# keypad.net
KiCad netlist of a schematic drawn in EAGLE
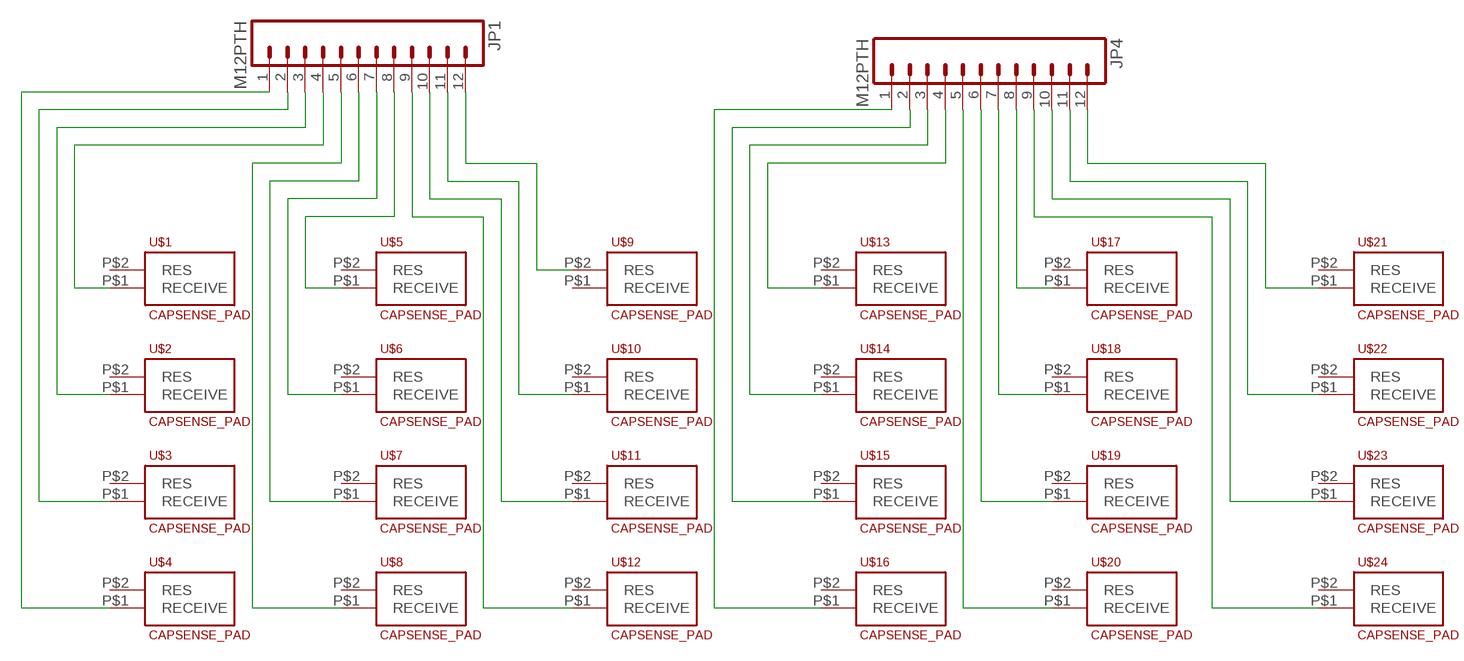
[diagram p0: schematic, sheet 1]

(export (version "E")
  (design (tool "Eeschema 10.0.6"))
  (components
    (comp (ref "JP1")
      (value "M12PTH")
      (footprint "eagle-import:1X12")
      (libsource (lib "eagle-import") (part "M12PTH"))
    )
    (comp (ref "JP4")
      (value "M12PTH")
      (footprint "eagle-import:1X12")
      (libsource (lib "eagle-import") (part "M12PTH"))
    )
    (comp (ref "U$1")
      (value "CAPSENSE_PAD")
      (footprint "eagle-import:CAPSENSE_PAD")
      (libsource (lib "eagle-import") (part "CAPSENSE_PAD"))
    )
    (comp (ref "U$2")
      (value "CAPSENSE_PAD")
      (footprint "eagle-import:CAPSENSE_PAD")
      (libsource (lib "eagle-import") (part "CAPSENSE_PAD"))
    )
    (comp (ref "U$3")
      (value "CAPSENSE_PAD")
      (footprint "eagle-import:CAPSENSE_PAD")
      (libsource (lib "eagle-import") (part "CAPSENSE_PAD"))
    )
    (comp (ref "U$4")
      (value "CAPSENSE_PAD")
      (footprint "eagle-import:CAPSENSE_PAD")
      (libsource (lib "eagle-import") (part "CAPSENSE_PAD"))
    )
    (comp (ref "U$5")
      (value "CAPSENSE_PAD")
      (footprint "eagle-import:CAPSENSE_PAD")
      (libsource (lib "eagle-import") (part "CAPSENSE_PAD"))
    )
    (comp (ref "U$6")
      (value "CAPSENSE_PAD")
      (footprint "eagle-import:CAPSENSE_PAD")
      (libsource (lib "eagle-import") (part "CAPSENSE_PAD"))
    )
    (comp (ref "U$7")
      (value "CAPSENSE_PAD")
      (footprint "eagle-import:CAPSENSE_PAD")
      (libsource (lib "eagle-import") (part "CAPSENSE_PAD"))
    )
    (comp (ref "U$8")
      (value "CAPSENSE_PAD")
      (footprint "eagle-import:CAPSENSE_PAD")
      (libsource (lib "eagle-import") (part "CAPSENSE_PAD"))
    )
    (comp (ref "U$9")
      (value "CAPSENSE_PAD")
      (footprint "eagle-import:CAPSENSE_PAD")
      (libsource (lib "eagle-import") (part "CAPSENSE_PAD"))
    )
    (comp (ref "U$10")
      (value "CAPSENSE_PAD")
      (footprint "eagle-import:CAPSENSE_PAD")
      (libsource (lib "eagle-import") (part "CAPSENSE_PAD"))
    )
    (comp (ref "U$11")
      (value "CAPSENSE_PAD")
      (footprint "eagle-import:CAPSENSE_PAD")
      (libsource (lib "eagle-import") (part "CAPSENSE_PAD"))
    )
    (comp (ref "U$12")
      (value "CAPSENSE_PAD")
      (footprint "eagle-import:CAPSENSE_PAD")
      (libsource (lib "eagle-import") (part "CAPSENSE_PAD"))
    )
    (comp (ref "U$13")
      (value "CAPSENSE_PAD")
      (footprint "eagle-import:CAPSENSE_PAD")
      (libsource (lib "eagle-import") (part "CAPSENSE_PAD"))
    )
    (comp (ref "U$14")
      (value "CAPSENSE_PAD")
      (footprint "eagle-import:CAPSENSE_PAD")
      (libsource (lib "eagle-import") (part "CAPSENSE_PAD"))
    )
    (comp (ref "U$15")
      (value "CAPSENSE_PAD")
      (footprint "eagle-import:CAPSENSE_PAD")
      (libsource (lib "eagle-import") (part "CAPSENSE_PAD"))
    )
    (comp (ref "U$16")
      (value "CAPSENSE_PAD")
      (footprint "eagle-import:CAPSENSE_PAD")
      (libsource (lib "eagle-import") (part "CAPSENSE_PAD"))
    )
    (comp (ref "U$17")
      (value "CAPSENSE_PAD")
      (footprint "eagle-import:CAPSENSE_PAD")
      (libsource (lib "eagle-import") (part "CAPSENSE_PAD"))
    )
    (comp (ref "U$18")
      (value "CAPSENSE_PAD")
      (footprint "eagle-import:CAPSENSE_PAD")
      (libsource (lib "eagle-import") (part "CAPSENSE_PAD"))
    )
    (comp (ref "U$19")
      (value "CAPSENSE_PAD")
      (footprint "eagle-import:CAPSENSE_PAD")
      (libsource (lib "eagle-import") (part "CAPSENSE_PAD"))
    )
    (comp (ref "U$20")
      (value "CAPSENSE_PAD")
      (footprint "eagle-import:CAPSENSE_PAD")
      (libsource (lib "eagle-import") (part "CAPSENSE_PAD"))
    )
    (comp (ref "U$21")
      (value "CAPSENSE_PAD")
      (footprint "eagle-import:CAPSENSE_PAD")
      (libsource (lib "eagle-import") (part "CAPSENSE_PAD"))
    )
    (comp (ref "U$22")
      (value "CAPSENSE_PAD")
      (footprint "eagle-import:CAPSENSE_PAD")
      (libsource (lib "eagle-import") (part "CAPSENSE_PAD"))
    )
    (comp (ref "U$23")
      (value "CAPSENSE_PAD")
      (footprint "eagle-import:CAPSENSE_PAD")
      (libsource (lib "eagle-import") (part "CAPSENSE_PAD"))
    )
    (comp (ref "U$24")
      (value "CAPSENSE_PAD")
      (footprint "eagle-import:CAPSENSE_PAD")
      (libsource (lib "eagle-import") (part "CAPSENSE_PAD"))
    )
  )
  (nets
    (net (code "1") (name "Net-(U$1-RECEIVE)") (class "Default")
      (node (ref "JP1") (pin "4") (pinfunction "4_4") (pintype "passive"))
      (node (ref "U$1") (pin "P$1") (pinfunction "RECEIVE_P$1") (pintype "bidirectional"))
    )
    (net (code "2") (name "Net-(U$2-RECEIVE)") (class "Default")
      (node (ref "JP1") (pin "3") (pinfunction "3_3") (pintype "passive"))
      (node (ref "U$2") (pin "P$1") (pinfunction "RECEIVE_P$1") (pintype "bidirectional"))
    )
    (net (code "3") (name "Net-(U$3-RECEIVE)") (class "Default")
      (node (ref "JP1") (pin "2") (pinfunction "2_2") (pintype "passive"))
      (node (ref "U$3") (pin "P$1") (pinfunction "RECEIVE_P$1") (pintype "bidirectional"))
    )
    (net (code "4") (name "Net-(U$4-RECEIVE)") (class "Default")
      (node (ref "JP1") (pin "1") (pinfunction "1_1") (pintype "passive"))
      (node (ref "U$4") (pin "P$1") (pinfunction "RECEIVE_P$1") (pintype "bidirectional"))
    )
    (net (code "5") (name "Net-(U$5-RECEIVE)") (class "Default")
      (node (ref "JP1") (pin "8") (pinfunction "8_8") (pintype "passive"))
      (node (ref "U$5") (pin "P$1") (pinfunction "RECEIVE_P$1") (pintype "bidirectional"))
    )
    (net (code "6") (name "Net-(U$6-RECEIVE)") (class "Default")
      (node (ref "JP1") (pin "7") (pinfunction "7_7") (pintype "passive"))
      (node (ref "U$6") (pin "P$1") (pinfunction "RECEIVE_P$1") (pintype "bidirectional"))
    )
    (net (code "7") (name "Net-(U$7-RECEIVE)") (class "Default")
      (node (ref "JP1") (pin "6") (pinfunction "6_6") (pintype "passive"))
      (node (ref "U$7") (pin "P$1") (pinfunction "RECEIVE_P$1") (pintype "bidirectional"))
    )
    (net (code "8") (name "Net-(U$8-RECEIVE)") (class "Default")
      (node (ref "JP1") (pin "5") (pinfunction "5_5") (pintype "passive"))
      (node (ref "U$8") (pin "P$1") (pinfunction "RECEIVE_P$1") (pintype "bidirectional"))
    )
    (net (code "9") (name "Net-(U$9-RES)") (class "Default")
      (node (ref "JP1") (pin "12") (pinfunction "12_12") (pintype "passive"))
      (node (ref "U$9") (pin "P$2") (pinfunction "RES_P$2") (pintype "bidirectional"))
    )
    (net (code "10") (name "Net-(U$10-RECEIVE)") (class "Default")
      (node (ref "JP1") (pin "11") (pinfunction "11_11") (pintype "passive"))
      (node (ref "U$10") (pin "P$1") (pinfunction "RECEIVE_P$1") (pintype "bidirectional"))
    )
    (net (code "11") (name "Net-(U$11-RECEIVE)") (class "Default")
      (node (ref "JP1") (pin "10") (pinfunction "10_10") (pintype "passive"))
      (node (ref "U$11") (pin "P$1") (pinfunction "RECEIVE_P$1") (pintype "bidirectional"))
    )
    (net (code "12") (name "Net-(U$12-RECEIVE)") (class "Default")
      (node (ref "JP1") (pin "9") (pinfunction "9_9") (pintype "passive"))
      (node (ref "U$12") (pin "P$1") (pinfunction "RECEIVE_P$1") (pintype "bidirectional"))
    )
    (net (code "13") (name "Net-(U$13-RECEIVE)") (class "Default")
      (node (ref "JP4") (pin "4") (pinfunction "4_4") (pintype "passive"))
      (node (ref "U$13") (pin "P$1") (pinfunction "RECEIVE_P$1") (pintype "bidirectional"))
    )
    (net (code "14") (name "Net-(U$14-RECEIVE)") (class "Default")
      (node (ref "JP4") (pin "3") (pinfunction "3_3") (pintype "passive"))
      (node (ref "U$14") (pin "P$1") (pinfunction "RECEIVE_P$1") (pintype "bidirectional"))
    )
    (net (code "15") (name "Net-(U$15-RECEIVE)") (class "Default")
      (node (ref "JP4") (pin "2") (pinfunction "2_2") (pintype "passive"))
      (node (ref "U$15") (pin "P$1") (pinfunction "RECEIVE_P$1") (pintype "bidirectional"))
    )
    (net (code "16") (name "Net-(U$16-RECEIVE)") (class "Default")
      (node (ref "JP4") (pin "1") (pinfunction "1_1") (pintype "passive"))
      (node (ref "U$16") (pin "P$1") (pinfunction "RECEIVE_P$1") (pintype "bidirectional"))
    )
    (net (code "17") (name "Net-(U$17-RECEIVE)") (class "Default")
      (node (ref "JP4") (pin "8") (pinfunction "8_8") (pintype "passive"))
      (node (ref "U$17") (pin "P$1") (pinfunction "RECEIVE_P$1") (pintype "bidirectional"))
    )
    (net (code "18") (name "Net-(U$18-RECEIVE)") (class "Default")
      (node (ref "JP4") (pin "7") (pinfunction "7_7") (pintype "passive"))
      (node (ref "U$18") (pin "P$1") (pinfunction "RECEIVE_P$1") (pintype "bidirectional"))
    )
    (net (code "19") (name "Net-(U$19-RECEIVE)") (class "Default")
      (node (ref "JP4") (pin "6") (pinfunction "6_6") (pintype "passive"))
      (node (ref "U$19") (pin "P$1") (pinfunction "RECEIVE_P$1") (pintype "bidirectional"))
    )
    (net (code "20") (name "Net-(U$20-RECEIVE)") (class "Default")
      (node (ref "JP4") (pin "5") (pinfunction "5_5") (pintype "passive"))
      (node (ref "U$20") (pin "P$1") (pinfunction "RECEIVE_P$1") (pintype "bidirectional"))
    )
    (net (code "21") (name "Net-(U$21-RECEIVE)") (class "Default")
      (node (ref "JP4") (pin "12") (pinfunction "12_12") (pintype "passive"))
      (node (ref "U$21") (pin "P$1") (pinfunction "RECEIVE_P$1") (pintype "bidirectional"))
    )
    (net (code "22") (name "Net-(U$22-RECEIVE)") (class "Default")
      (node (ref "JP4") (pin "11") (pinfunction "11_11") (pintype "passive"))
      (node (ref "U$22") (pin "P$1") (pinfunction "RECEIVE_P$1") (pintype "bidirectional"))
    )
    (net (code "23") (name "Net-(U$23-RECEIVE)") (class "Default")
      (node (ref "JP4") (pin "10") (pinfunction "10_10") (pintype "passive"))
      (node (ref "U$23") (pin "P$1") (pinfunction "RECEIVE_P$1") (pintype "bidirectional"))
    )
    (net (code "24") (name "Net-(U$24-RECEIVE)") (class "Default")
      (node (ref "JP4") (pin "9") (pinfunction "9_9") (pintype "passive"))
      (node (ref "U$24") (pin "P$1") (pinfunction "RECEIVE_P$1") (pintype "bidirectional"))
    )
    (net (code "25") (name "unconnected-(U$1-RES-PadP$2)") (class "Default")
      (node (ref "U$1") (pin "P$2") (pinfunction "RES_P$2") (pintype "bidirectional"))
    )
    (net (code "26") (name "unconnected-(U$2-RES-PadP$2)") (class "Default")
      (node (ref "U$2") (pin "P$2") (pinfunction "RES_P$2") (pintype "bidirectional"))
    )
    (net (code "27") (name "unconnected-(U$3-RES-PadP$2)") (class "Default")
      (node (ref "U$3") (pin "P$2") (pinfunction "RES_P$2") (pintype "bidirectional"))
    )
    (net (code "28") (name "unconnected-(U$4-RES-PadP$2)") (class "Default")
      (node (ref "U$4") (pin "P$2") (pinfunction "RES_P$2") (pintype "bidirectional"))
    )
    (net (code "29") (name "unconnected-(U$5-RES-PadP$2)") (class "Default")
      (node (ref "U$5") (pin "P$2") (pinfunction "RES_P$2") (pintype "bidirectional"))
    )
    (net (code "30") (name "unconnected-(U$6-RES-PadP$2)") (class "Default")
      (node (ref "U$6") (pin "P$2") (pinfunction "RES_P$2") (pintype "bidirectional"))
    )
    (net (code "31") (name "unconnected-(U$7-RES-PadP$2)") (class "Default")
      (node (ref "U$7") (pin "P$2") (pinfunction "RES_P$2") (pintype "bidirectional"))
    )
    (net (code "32") (name "unconnected-(U$8-RES-PadP$2)") (class "Default")
      (node (ref "U$8") (pin "P$2") (pinfunction "RES_P$2") (pintype "bidirectional"))
    )
    (net (code "33") (name "unconnected-(U$9-RECEIVE-PadP$1)") (class "Default")
      (node (ref "U$9") (pin "P$1") (pinfunction "RECEIVE_P$1") (pintype "bidirectional"))
    )
    (net (code "34") (name "unconnected-(U$10-RES-PadP$2)") (class "Default")
      (node (ref "U$10") (pin "P$2") (pinfunction "RES_P$2") (pintype "bidirectional"))
    )
    (net (code "35") (name "unconnected-(U$11-RES-PadP$2)") (class "Default")
      (node (ref "U$11") (pin "P$2") (pinfunction "RES_P$2") (pintype "bidirectional"))
    )
    (net (code "36") (name "unconnected-(U$12-RES-PadP$2)") (class "Default")
      (node (ref "U$12") (pin "P$2") (pinfunction "RES_P$2") (pintype "bidirectional"))
    )
    (net (code "37") (name "unconnected-(U$13-RES-PadP$2)") (class "Default")
      (node (ref "U$13") (pin "P$2") (pinfunction "RES_P$2") (pintype "bidirectional"))
    )
    (net (code "38") (name "unconnected-(U$14-RES-PadP$2)") (class "Default")
      (node (ref "U$14") (pin "P$2") (pinfunction "RES_P$2") (pintype "bidirectional"))
    )
    (net (code "39") (name "unconnected-(U$15-RES-PadP$2)") (class "Default")
      (node (ref "U$15") (pin "P$2") (pinfunction "RES_P$2") (pintype "bidirectional"))
    )
    (net (code "40") (name "unconnected-(U$16-RES-PadP$2)") (class "Default")
      (node (ref "U$16") (pin "P$2") (pinfunction "RES_P$2") (pintype "bidirectional"))
    )
    (net (code "41") (name "unconnected-(U$17-RES-PadP$2)") (class "Default")
      (node (ref "U$17") (pin "P$2") (pinfunction "RES_P$2") (pintype "bidirectional"))
    )
    (net (code "42") (name "unconnected-(U$18-RES-PadP$2)") (class "Default")
      (node (ref "U$18") (pin "P$2") (pinfunction "RES_P$2") (pintype "bidirectional"))
    )
    (net (code "43") (name "unconnected-(U$19-RES-PadP$2)") (class "Default")
      (node (ref "U$19") (pin "P$2") (pinfunction "RES_P$2") (pintype "bidirectional"))
    )
    (net (code "44") (name "unconnected-(U$20-RES-PadP$2)") (class "Default")
      (node (ref "U$20") (pin "P$2") (pinfunction "RES_P$2") (pintype "bidirectional"))
    )
    (net (code "45") (name "unconnected-(U$21-RES-PadP$2)") (class "Default")
      (node (ref "U$21") (pin "P$2") (pinfunction "RES_P$2") (pintype "bidirectional"))
    )
    (net (code "46") (name "unconnected-(U$22-RES-PadP$2)") (class "Default")
      (node (ref "U$22") (pin "P$2") (pinfunction "RES_P$2") (pintype "bidirectional"))
    )
    (net (code "47") (name "unconnected-(U$23-RES-PadP$2)") (class "Default")
      (node (ref "U$23") (pin "P$2") (pinfunction "RES_P$2") (pintype "bidirectional"))
    )
    (net (code "48") (name "unconnected-(U$24-RES-PadP$2)") (class "Default")
      (node (ref "U$24") (pin "P$2") (pinfunction "RES_P$2") (pintype "bidirectional"))
    )
  )
)
